# Master_board.net
KiCad netlist of a schematic drawn in EAGLE
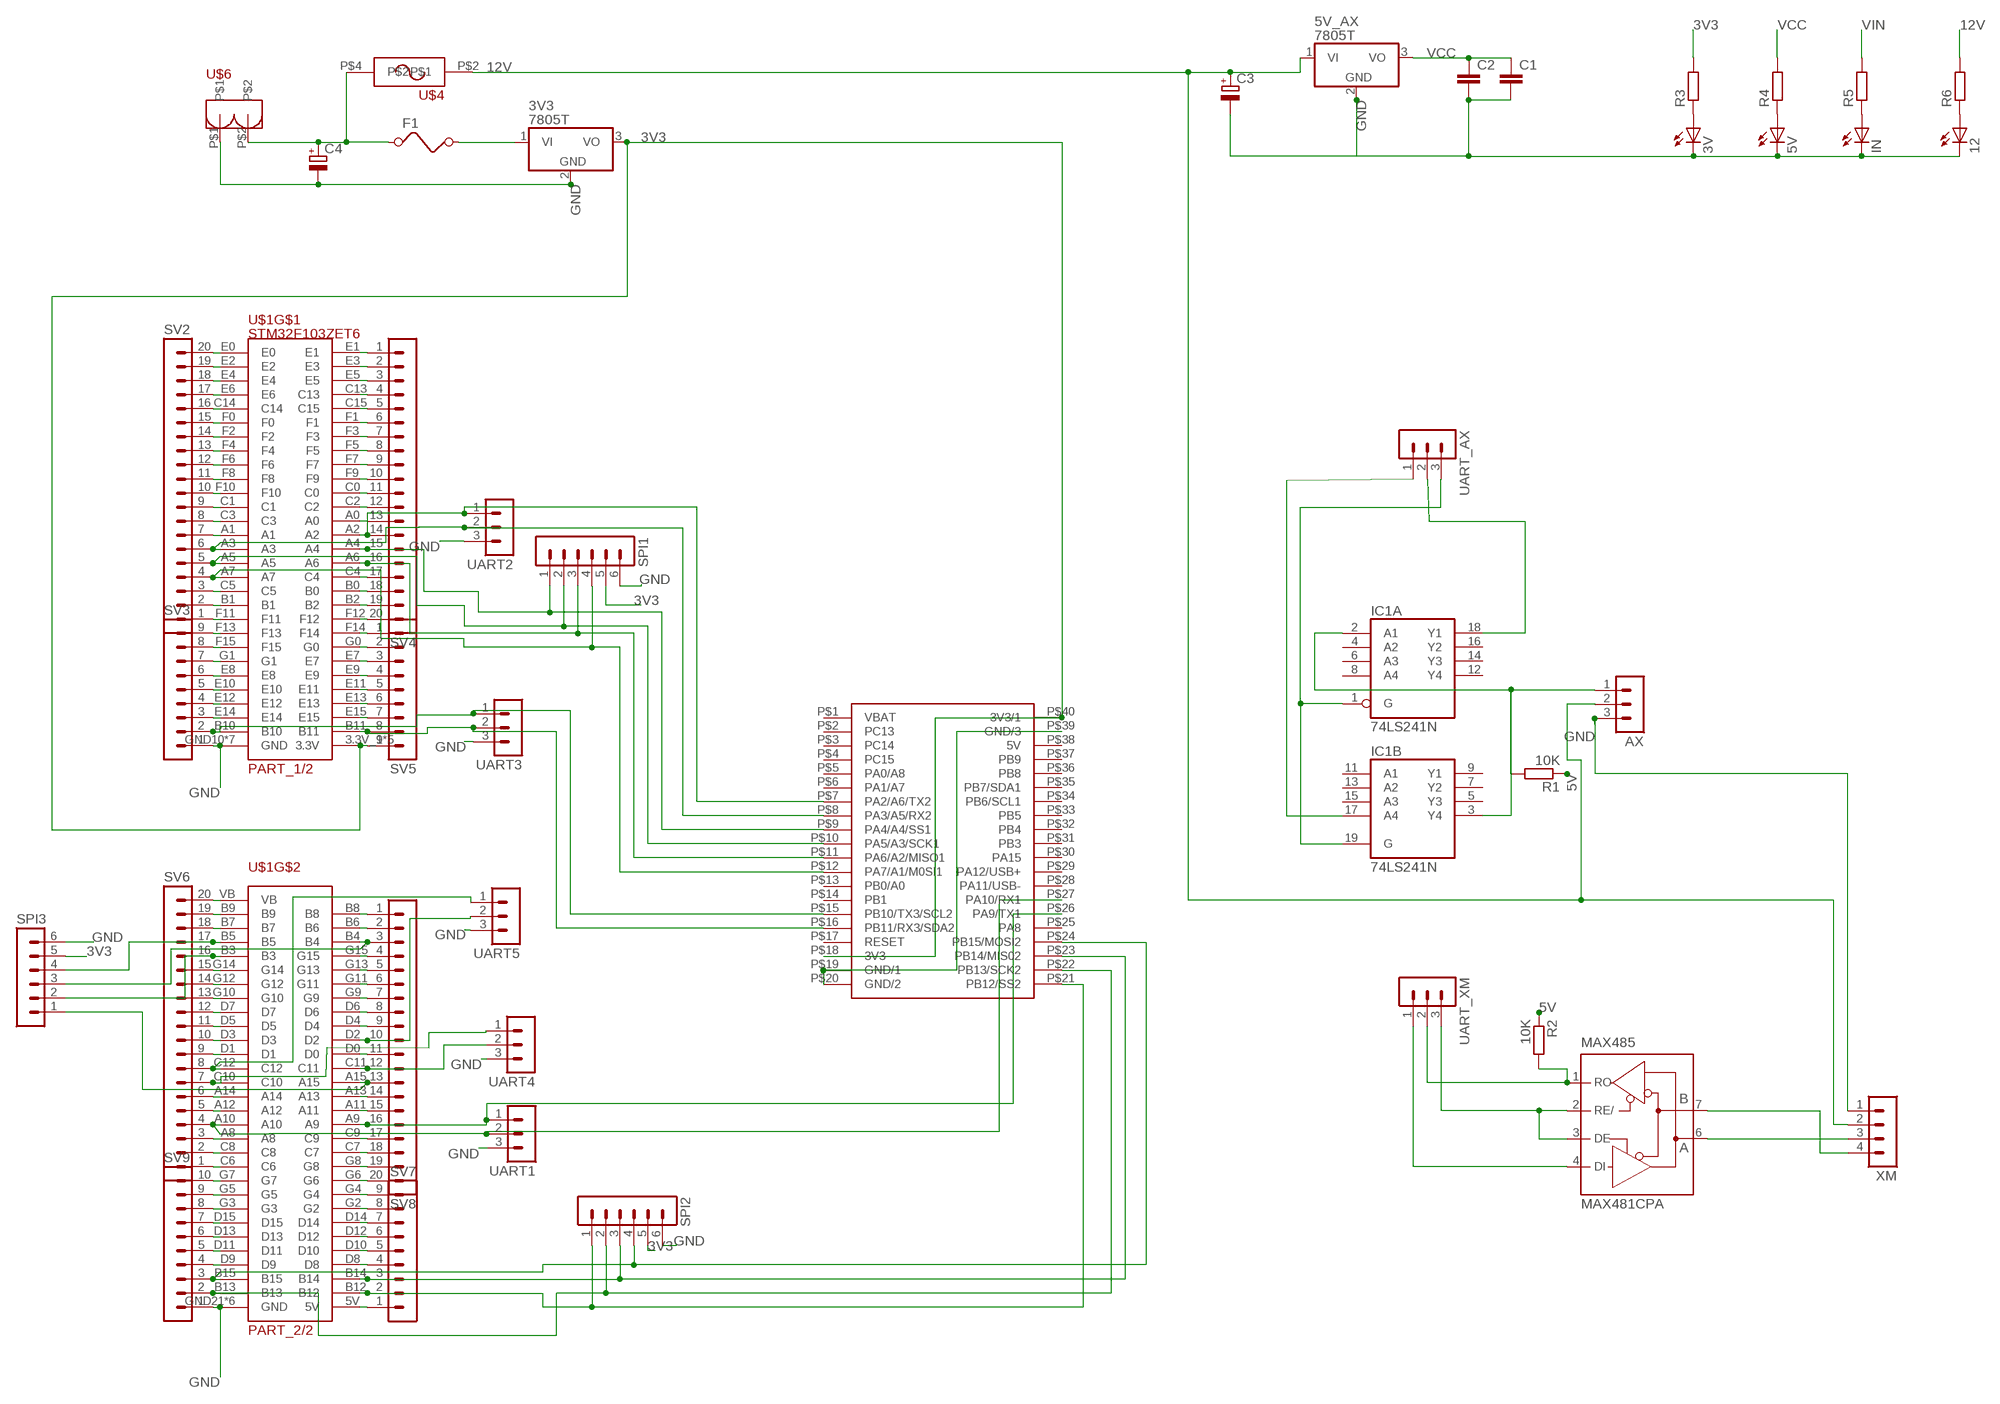
[diagram p0: schematic, sheet 1]

(export (version "E")
  (design (tool "Eeschema 10.0.6"))
  (components
    (comp (ref "3V")
      (value "LED_ELD260")
      (footprint "eagle-import:LED_LD260")
      (libsource (lib "eagle-import") (part "LED_ELD260"))
    )
    (comp (ref "3V3")
      (value "7805T")
      (footprint "eagle-import:TO220H")
      (libsource (lib "eagle-import") (part "78T05"))
    )
    (comp (ref "5V")
      (value "LED_ELD260")
      (footprint "eagle-import:LED_LD260")
      (libsource (lib "eagle-import") (part "LED_ELD260"))
    )
    (comp (ref "5V_AX")
      (value "7805T")
      (footprint "eagle-import:TO220H")
      (libsource (lib "eagle-import") (part "78T05"))
    )
    (comp (ref "12")
      (value "LED_ELD260")
      (footprint "eagle-import:LED_LD260")
      (libsource (lib "eagle-import") (part "LED_ELD260"))
    )
    (comp (ref "AX")
      (value "MA03-1")
      (footprint "eagle-import:MA03-1")
      (libsource (lib "eagle-import") (part "MA03-1"))
    )
    (comp (ref "C1")
      (value "C-EU025-024X044")
      (footprint "eagle-import:C025-024X044")
      (libsource (lib "eagle-import") (part "C-EU025-024X044"))
    )
    (comp (ref "C2")
      (value "C-EU025-024X044")
      (footprint "eagle-import:C025-024X044")
      (libsource (lib "eagle-import") (part "C-EU025-024X044"))
    )
    (comp (ref "C3")
      (value "CPOL-EUE5-10.5")
      (footprint "eagle-import:E5-10,5")
      (libsource (lib "eagle-import") (part "CPOL-EUE5-10.5"))
    )
    (comp (ref "C4")
      (value "CPOL-EUE5-10.5")
      (footprint "eagle-import:E5-10,5")
      (libsource (lib "eagle-import") (part "CPOL-EUE5-10.5"))
    )
    (comp (ref "F1")
      (value "FUSE")
      (footprint "eagle-import:FUSE")
      (libsource (lib "eagle-import") (part "FUSE"))
    )
    (comp (ref "IC1")
      (value "74LS241N")
      (footprint "eagle-import:DIL20")
      (libsource (lib "eagle-import") (part "74241NLS"))
    )
    (comp (ref "IN")
      (value "LED_ELD260")
      (footprint "eagle-import:LED_LD260")
      (libsource (lib "eagle-import") (part "LED_ELD260"))
    )
    (comp (ref "MAX485")
      (value "MAX481CPA")
      (footprint "eagle-import:DIL08")
      (fields (field (name "MPN") "MAX481CPA+"))
      (libsource (lib "eagle-import") (part "MAX481CPA"))
    )
    (comp (ref "R1")
      (value "10K")
      (footprint "eagle-import:0309_12")
      (libsource (lib "eagle-import") (part "R-EU_0309/12"))
    )
    (comp (ref "R2")
      (value "10K")
      (footprint "eagle-import:0309_12")
      (libsource (lib "eagle-import") (part "R-EU_0309/12"))
    )
    (comp (ref "R3")
      (value "R-EU_0204/5")
      (footprint "eagle-import:0204_5")
      (libsource (lib "eagle-import") (part "resistor_348_R-EU_0204/5"))
    )
    (comp (ref "R4")
      (value "R-EU_0204/5")
      (footprint "eagle-import:0204_5")
      (libsource (lib "eagle-import") (part "resistor_348_R-EU_0204/5"))
    )
    (comp (ref "R5")
      (value "R-EU_0204/5")
      (footprint "eagle-import:0204_5")
      (libsource (lib "eagle-import") (part "resistor_348_R-EU_0204/5"))
    )
    (comp (ref "R6")
      (value "R-EU_0204/5")
      (footprint "eagle-import:0204_5")
      (libsource (lib "eagle-import") (part "resistor_348_R-EU_0204/5"))
    )
    (comp (ref "SPI1")
      (value "MA06-1")
      (footprint "eagle-import:MA06-1")
      (libsource (lib "eagle-import") (part "MA06-1"))
    )
    (comp (ref "SPI2")
      (value "MA06-1")
      (footprint "eagle-import:MA06-1")
      (libsource (lib "eagle-import") (part "MA06-1"))
    )
    (comp (ref "SPI3")
      (value "MA06-1")
      (footprint "eagle-import:MA06-1")
      (libsource (lib "eagle-import") (part "MA06-1"))
    )
    (comp (ref "SV2")
      (value "MA20-1L")
      (footprint "eagle-import:MA20-1L")
      (libsource (lib "eagle-import") (part "MA20-1L"))
    )
    (comp (ref "SV3")
      (value "MA09-1")
      (footprint "eagle-import:MA09-1")
      (libsource (lib "eagle-import") (part "MA09-1"))
    )
    (comp (ref "SV4")
      (value "MA20-1L")
      (footprint "eagle-import:MA20-1L")
      (libsource (lib "eagle-import") (part "MA20-1L"))
    )
    (comp (ref "SV5")
      (value "MA09-1")
      (footprint "eagle-import:MA09-1")
      (libsource (lib "eagle-import") (part "MA09-1"))
    )
    (comp (ref "SV6")
      (value "MA20-1L")
      (footprint "eagle-import:MA20-1L")
      (libsource (lib "eagle-import") (part "MA20-1L"))
    )
    (comp (ref "SV7")
      (value "MA09-1")
      (footprint "eagle-import:MA09-1")
      (libsource (lib "eagle-import") (part "MA09-1"))
    )
    (comp (ref "SV8")
      (value "MA20-1L")
      (footprint "eagle-import:MA20-1L")
      (libsource (lib "eagle-import") (part "MA20-1L"))
    )
    (comp (ref "SV9")
      (value "MA10-1")
      (footprint "eagle-import:MA10-1")
      (libsource (lib "eagle-import") (part "MA10-1"))
    )
    (comp (ref "U$1")
      (value "M32F103ZET6_DEV_BOARD")
      (footprint "eagle-import:STM32F103ZET6_DEV_BOARD")
      (libsource (lib "eagle-import") (part "M32F103ZET6_DEV_BOARD"))
    )
    (comp (ref "U$2")
      (value "BLUEPILL")
      (footprint "eagle-import:BLUEPILL")
      (libsource (lib "eagle-import") (part "BLUEPILL"))
    )
    (comp (ref "U$4")
      (value "AUTO_FUSE")
      (footprint "eagle-import:AUTO_FUSE")
      (libsource (lib "eagle-import") (part "AUTO_FUSE"))
    )
    (comp (ref "U$6")
      (value "GREEN_HEADER")
      (footprint "eagle-import:GREEN_HEADER")
      (libsource (lib "eagle-import") (part "GREEN_HEADER"))
    )
    (comp (ref "UART1")
      (value "MA03-1")
      (footprint "eagle-import:MA03-1")
      (libsource (lib "eagle-import") (part "MA03-1"))
    )
    (comp (ref "UART2")
      (value "MA03-1")
      (footprint "eagle-import:MA03-1")
      (libsource (lib "eagle-import") (part "MA03-1"))
    )
    (comp (ref "UART3")
      (value "MA03-1")
      (footprint "eagle-import:MA03-1")
      (libsource (lib "eagle-import") (part "MA03-1"))
    )
    (comp (ref "UART4")
      (value "MA03-1")
      (footprint "eagle-import:MA03-1")
      (libsource (lib "eagle-import") (part "MA03-1"))
    )
    (comp (ref "UART5")
      (value "MA03-1")
      (footprint "eagle-import:MA03-1")
      (libsource (lib "eagle-import") (part "MA03-1"))
    )
    (comp (ref "UART_AX")
      (value "MA03-1")
      (footprint "eagle-import:MA03-1")
      (libsource (lib "eagle-import") (part "MA03-1"))
    )
    (comp (ref "UART_XM")
      (value "MA03-1")
      (footprint "eagle-import:MA03-1")
      (libsource (lib "eagle-import") (part "MA03-1"))
    )
    (comp (ref "XM")
      (value "MA04-1")
      (footprint "eagle-import:MA04-1")
      (libsource (lib "eagle-import") (part "MA04-1"))
    )
  )
  (nets
    (net (code "1") (name "/3V3") (class "Default")
      (node (ref "3V3") (pin "3") (pinfunction "VO_3") (pintype "passive"))
      (node (ref "R3") (pin "2") (pinfunction "2_2") (pintype "passive"))
      (node (ref "SPI1") (pin "5") (pinfunction "5_5") (pintype "passive"))
      (node (ref "SPI2") (pin "5") (pinfunction "5_5") (pintype "passive"))
      (node (ref "SPI3") (pin "5") (pinfunction "5_5") (pintype "passive"))
      (node (ref "SV5") (pin "9") (pinfunction "9_9") (pintype "passive"))
      (node (ref "U$1") (pin "3.3V_1") (pinfunction "3.3V_3.3V_1") (pintype "bidirectional"))
      (node (ref "U$1") (pin "3.3V_2") (pinfunction "3.3V_3.3V_2") (pintype "bidirectional"))
      (node (ref "U$1") (pin "3.3V_3") (pinfunction "3.3V_3.3V_3") (pintype "bidirectional"))
      (node (ref "U$1") (pin "3.3V_4") (pinfunction "3.3V_3.3V_4") (pintype "bidirectional"))
      (node (ref "U$1") (pin "3.3V_5") (pinfunction "3.3V_3.3V_5") (pintype "bidirectional"))
      (node (ref "U$2") (pin "P$18") (pinfunction "3V3_P$18") (pintype "bidirectional"))
      (node (ref "U$2") (pin "P$40") (pinfunction "3V3/1_P$40") (pintype "bidirectional"))
    )
    (net (code "2") (name "/5V") (class "Default")
      (node (ref "R1") (pin "1") (pinfunction "1_1") (pintype "passive"))
      (node (ref "R2") (pin "1") (pinfunction "1_1") (pintype "passive"))
    )
    (net (code "3") (name "/12V") (class "Default")
      (node (ref "5V_AX") (pin "1") (pinfunction "VI_1") (pintype "input"))
      (node (ref "AX") (pin "2") (pinfunction "2_2") (pintype "passive"))
      (node (ref "C3") (pin "+") (pinfunction "+_+") (pintype "passive"))
      (node (ref "R6") (pin "2") (pinfunction "2_2") (pintype "passive"))
      (node (ref "U$4") (pin "P$2") (pinfunction "P$1_P$2") (pintype "bidirectional"))
      (node (ref "XM") (pin "2") (pinfunction "2_2") (pintype "passive"))
    )
    (net (code "4") (name "/GND") (class "Default")
      (node (ref "12") (pin "K") (pinfunction "C_K") (pintype "passive"))
      (node (ref "3V") (pin "K") (pinfunction "C_K") (pintype "passive"))
      (node (ref "3V3") (pin "2") (pinfunction "GND_2") (pintype "passive"))
      (node (ref "5V") (pin "K") (pinfunction "C_K") (pintype "passive"))
      (node (ref "5V_AX") (pin "2") (pinfunction "GND_2") (pintype "passive"))
      (node (ref "AX") (pin "3") (pinfunction "3_3") (pintype "passive"))
      (node (ref "C1") (pin "2") (pinfunction "2_2") (pintype "passive"))
      (node (ref "C2") (pin "2") (pinfunction "2_2") (pintype "passive"))
      (node (ref "C3") (pin "-") (pinfunction "-_-") (pintype "passive"))
      (node (ref "C4") (pin "-") (pinfunction "-_-") (pintype "passive"))
      (node (ref "IN") (pin "K") (pinfunction "C_K") (pintype "passive"))
      (node (ref "SPI1") (pin "6") (pinfunction "6_6") (pintype "passive"))
      (node (ref "SPI2") (pin "6") (pinfunction "6_6") (pintype "passive"))
      (node (ref "SPI3") (pin "6") (pinfunction "6_6") (pintype "passive"))
      (node (ref "SV3") (pin "1") (pinfunction "1_1") (pintype "passive"))
      (node (ref "SV9") (pin "1") (pinfunction "1_1") (pintype "passive"))
      (node (ref "U$1") (pin "GND10") (pinfunction "GND_GND10") (pintype "bidirectional"))
      (node (ref "U$1") (pin "GND11") (pinfunction "GND_GND11") (pintype "bidirectional"))
      (node (ref "U$1") (pin "GND12") (pinfunction "GND_GND12") (pintype "bidirectional"))
      (node (ref "U$1") (pin "GND13") (pinfunction "GND_GND13") (pintype "bidirectional"))
      (node (ref "U$1") (pin "GND14") (pinfunction "GND_GND14") (pintype "bidirectional"))
      (node (ref "U$1") (pin "GND15") (pinfunction "GND_GND15") (pintype "bidirectional"))
      (node (ref "U$1") (pin "GND16") (pinfunction "GND_GND16") (pintype "bidirectional"))
      (node (ref "U$1") (pin "GND21") (pinfunction "GND_GND21") (pintype "bidirectional"))
      (node (ref "U$1") (pin "GND22") (pinfunction "GND_GND22") (pintype "bidirectional"))
      (node (ref "U$1") (pin "GND24") (pinfunction "GND_GND24") (pintype "bidirectional"))
      (node (ref "U$1") (pin "GND25") (pinfunction "GND_GND25") (pintype "bidirectional"))
      (node (ref "U$1") (pin "GND26") (pinfunction "GND_GND26") (pintype "bidirectional"))
      (node (ref "U$1") (pin "GND_20") (pinfunction "GND_GND_20") (pintype "bidirectional"))
      (node (ref "U$2") (pin "P$19") (pinfunction "GND/1_P$19") (pintype "bidirectional"))
      (node (ref "U$2") (pin "P$20") (pinfunction "GND/2_P$20") (pintype "bidirectional"))
      (node (ref "U$2") (pin "P$39") (pinfunction "GND/3_P$39") (pintype "bidirectional"))
      (node (ref "U$6") (pin "P$1") (pinfunction "P$1_P$1") (pintype "bidirectional"))
      (node (ref "UART1") (pin "3") (pinfunction "3_3") (pintype "passive"))
      (node (ref "UART2") (pin "3") (pinfunction "3_3") (pintype "passive"))
      (node (ref "UART3") (pin "3") (pinfunction "3_3") (pintype "passive"))
      (node (ref "UART4") (pin "3") (pinfunction "3_3") (pintype "passive"))
      (node (ref "UART5") (pin "3") (pinfunction "3_3") (pintype "passive"))
      (node (ref "XM") (pin "1") (pinfunction "1_1") (pintype "passive"))
    )
    (net (code "5") (name "/VCC") (class "Default")
      (node (ref "5V_AX") (pin "3") (pinfunction "VO_3") (pintype "passive"))
      (node (ref "C1") (pin "1") (pinfunction "1_1") (pintype "passive"))
      (node (ref "C2") (pin "1") (pinfunction "1_1") (pintype "passive"))
      (node (ref "R4") (pin "2") (pinfunction "2_2") (pintype "passive"))
    )
    (net (code "6") (name "/VIN") (class "Default")
      (node (ref "C4") (pin "+") (pinfunction "+_+") (pintype "passive"))
      (node (ref "F1") (pin "1") (pinfunction "1_1") (pintype "passive"))
      (node (ref "R5") (pin "2") (pinfunction "2_2") (pintype "passive"))
      (node (ref "U$4") (pin "P$4") (pinfunction "P$2_P$4") (pintype "bidirectional"))
      (node (ref "U$6") (pin "P$2") (pinfunction "P$2_P$2") (pintype "bidirectional"))
    )
    (net (code "7") (name "Net-(3V-PadA)") (class "Default")
      (node (ref "3V") (pin "A") (pinfunction "A_A") (pintype "passive"))
      (node (ref "R3") (pin "1") (pinfunction "1_1") (pintype "passive"))
    )
    (net (code "8") (name "Net-(3V3-VI)") (class "Default")
      (node (ref "3V3") (pin "1") (pinfunction "VI_1") (pintype "input"))
      (node (ref "F1") (pin "2") (pinfunction "2_2") (pintype "passive"))
    )
    (net (code "9") (name "Net-(5V-PadA)") (class "Default")
      (node (ref "5V") (pin "A") (pinfunction "A_A") (pintype "passive"))
      (node (ref "R4") (pin "1") (pinfunction "1_1") (pintype "passive"))
    )
    (net (code "10") (name "Net-(12-PadA)") (class "Default")
      (node (ref "12") (pin "A") (pinfunction "A_A") (pintype "passive"))
      (node (ref "R6") (pin "1") (pinfunction "1_1") (pintype "passive"))
    )
    (net (code "11") (name "Net-(IC1A-A1)") (class "Default")
      (node (ref "AX") (pin "1") (pinfunction "1_1") (pintype "passive"))
      (node (ref "IC1") (pin "2") (pinfunction "A1_2") (pintype "input"))
      (node (ref "IC1") (pin "3") (pinfunction "Y4_3") (pintype "tri_state"))
      (node (ref "R1") (pin "2") (pinfunction "2_2") (pintype "passive"))
    )
    (net (code "12") (name "Net-(IC1A-G)") (class "Default")
      (node (ref "IC1") (pin "1") (pinfunction "G_1") (pintype "input"))
      (node (ref "IC1") (pin "19") (pinfunction "G_19") (pintype "input"))
      (node (ref "UART_AX") (pin "3") (pinfunction "3_3") (pintype "passive"))
    )
    (net (code "13") (name "Net-(IC1A-Y1)") (class "Default")
      (node (ref "IC1") (pin "18") (pinfunction "Y1_18") (pintype "tri_state"))
      (node (ref "UART_AX") (pin "2") (pinfunction "2_2") (pintype "passive"))
    )
    (net (code "14") (name "Net-(IC1B-A4)") (class "Default")
      (node (ref "IC1") (pin "17") (pinfunction "A4_17") (pintype "input"))
      (node (ref "UART_AX") (pin "1") (pinfunction "1_1") (pintype "passive"))
    )
    (net (code "15") (name "Net-(IN-PadA)") (class "Default")
      (node (ref "IN") (pin "A") (pinfunction "A_A") (pintype "passive"))
      (node (ref "R5") (pin "1") (pinfunction "1_1") (pintype "passive"))
    )
    (net (code "16") (name "Net-(MAX485A-A)") (class "Default")
      (node (ref "MAX485") (pin "6") (pinfunction "A_6") (pintype "passive"))
      (node (ref "XM") (pin "3") (pinfunction "3_3") (pintype "passive"))
    )
    (net (code "17") (name "Net-(MAX485A-B)") (class "Default")
      (node (ref "MAX485") (pin "7") (pinfunction "B_7") (pintype "passive"))
      (node (ref "XM") (pin "4") (pinfunction "4_4") (pintype "passive"))
    )
    (net (code "18") (name "Net-(MAX485A-DE)") (class "Default")
      (node (ref "MAX485") (pin "2") (pinfunction "RE/_2") (pintype "input"))
      (node (ref "MAX485") (pin "3") (pinfunction "DE_3") (pintype "input"))
      (node (ref "UART_XM") (pin "3") (pinfunction "3_3") (pintype "passive"))
    )
    (net (code "19") (name "Net-(MAX485A-DI)") (class "Default")
      (node (ref "MAX485") (pin "4") (pinfunction "DI_4") (pintype "input"))
      (node (ref "UART_XM") (pin "1") (pinfunction "1_1") (pintype "passive"))
    )
    (net (code "20") (name "Net-(MAX485A-RO)") (class "Default")
      (node (ref "MAX485") (pin "1") (pinfunction "RO_1") (pintype "output"))
      (node (ref "R2") (pin "2") (pinfunction "2_2") (pintype "passive"))
      (node (ref "UART_XM") (pin "2") (pinfunction "2_2") (pintype "passive"))
    )
    (net (code "21") (name "Net-(SPI3-Pad1)") (class "Default")
      (node (ref "SPI3") (pin "1") (pinfunction "1_1") (pintype "passive"))
      (node (ref "SV8") (pin "13") (pinfunction "13_13") (pintype "passive"))
      (node (ref "U$1") (pin "A15") (pinfunction "A15_A15") (pintype "bidirectional"))
    )
    (net (code "22") (name "Net-(SPI3-Pad2)") (class "Default")
      (node (ref "SPI3") (pin "2") (pinfunction "2_2") (pintype "passive"))
      (node (ref "SV6") (pin "16") (pinfunction "16_16") (pintype "passive"))
      (node (ref "U$1") (pin "B3") (pinfunction "B3_B3") (pintype "bidirectional"))
    )
    (net (code "23") (name "Net-(SPI3-Pad3)") (class "Default")
      (node (ref "SPI3") (pin "3") (pinfunction "3_3") (pintype "passive"))
      (node (ref "SV8") (pin "3") (pinfunction "3_3") (pintype "passive"))
      (node (ref "U$1") (pin "B4") (pinfunction "B4_B4") (pintype "bidirectional"))
    )
    (net (code "24") (name "Net-(SPI3-Pad4)") (class "Default")
      (node (ref "SPI3") (pin "4") (pinfunction "4_4") (pintype "passive"))
      (node (ref "SV6") (pin "17") (pinfunction "17_17") (pintype "passive"))
      (node (ref "U$1") (pin "B5") (pinfunction "B5_B5") (pintype "bidirectional"))
    )
    (net (code "25") (name "Net-(SV2-Pad1)") (class "Default")
      (node (ref "SV2") (pin "1") (pinfunction "1_1") (pintype "passive"))
      (node (ref "U$1") (pin "F11") (pinfunction "F11_F11") (pintype "bidirectional"))
    )
    (net (code "26") (name "Net-(SV2-Pad2)") (class "Default")
      (node (ref "SV2") (pin "2") (pinfunction "2_2") (pintype "passive"))
      (node (ref "U$1") (pin "B1") (pinfunction "B1_B1") (pintype "bidirectional"))
    )
    (net (code "27") (name "Net-(SV2-Pad3)") (class "Default")
      (node (ref "SV2") (pin "3") (pinfunction "3_3") (pintype "passive"))
      (node (ref "U$1") (pin "C5") (pinfunction "C5_C5") (pintype "bidirectional"))
    )
    (net (code "28") (name "Net-(SV2-Pad7)") (class "Default")
      (node (ref "SV2") (pin "7") (pinfunction "7_7") (pintype "passive"))
      (node (ref "U$1") (pin "A1") (pinfunction "A1_A1") (pintype "bidirectional"))
    )
    (net (code "29") (name "Net-(SV2-Pad8)") (class "Default")
      (node (ref "SV2") (pin "8") (pinfunction "8_8") (pintype "passive"))
      (node (ref "U$1") (pin "C3") (pinfunction "C3_C3") (pintype "bidirectional"))
    )
    (net (code "30") (name "Net-(SV2-Pad9)") (class "Default")
      (node (ref "SV2") (pin "9") (pinfunction "9_9") (pintype "passive"))
      (node (ref "U$1") (pin "C1") (pinfunction "C1_C1") (pintype "bidirectional"))
    )
    (net (code "31") (name "Net-(SV2-Pad10)") (class "Default")
      (node (ref "SV2") (pin "10") (pinfunction "10_10") (pintype "passive"))
      (node (ref "U$1") (pin "F10") (pinfunction "F10_F10") (pintype "bidirectional"))
    )
    (net (code "32") (name "Net-(SV2-Pad11)") (class "Default")
      (node (ref "SV2") (pin "11") (pinfunction "11_11") (pintype "passive"))
      (node (ref "U$1") (pin "F8") (pinfunction "F8_F8") (pintype "bidirectional"))
    )
    (net (code "33") (name "Net-(SV2-Pad12)") (class "Default")
      (node (ref "SV2") (pin "12") (pinfunction "12_12") (pintype "passive"))
      (node (ref "U$1") (pin "F6") (pinfunction "F6_F6") (pintype "bidirectional"))
    )
    (net (code "34") (name "Net-(SV2-Pad13)") (class "Default")
      (node (ref "SV2") (pin "13") (pinfunction "13_13") (pintype "passive"))
      (node (ref "U$1") (pin "F4") (pinfunction "F4_F4") (pintype "bidirectional"))
    )
    (net (code "35") (name "Net-(SV2-Pad14)") (class "Default")
      (node (ref "SV2") (pin "14") (pinfunction "14_14") (pintype "passive"))
      (node (ref "U$1") (pin "F2") (pinfunction "F2_F2") (pintype "bidirectional"))
    )
    (net (code "36") (name "Net-(SV2-Pad15)") (class "Default")
      (node (ref "SV2") (pin "15") (pinfunction "15_15") (pintype "passive"))
      (node (ref "U$1") (pin "F0") (pinfunction "F0_F0") (pintype "bidirectional"))
    )
    (net (code "37") (name "Net-(SV2-Pad16)") (class "Default")
      (node (ref "SV2") (pin "16") (pinfunction "16_16") (pintype "passive"))
      (node (ref "U$1") (pin "C14") (pinfunction "C14_C14") (pintype "bidirectional"))
    )
    (net (code "38") (name "Net-(SV2-Pad17)") (class "Default")
      (node (ref "SV2") (pin "17") (pinfunction "17_17") (pintype "passive"))
      (node (ref "U$1") (pin "E6") (pinfunction "E6_E6") (pintype "bidirectional"))
    )
    (net (code "39") (name "Net-(SV2-Pad18)") (class "Default")
      (node (ref "SV2") (pin "18") (pinfunction "18_18") (pintype "passive"))
      (node (ref "U$1") (pin "E4") (pinfunction "E4_E4") (pintype "bidirectional"))
    )
    (net (code "40") (name "Net-(SV2-Pad19)") (class "Default")
      (node (ref "SV2") (pin "19") (pinfunction "19_19") (pintype "passive"))
      (node (ref "U$1") (pin "E2") (pinfunction "E2_E2") (pintype "bidirectional"))
    )
    (net (code "41") (name "Net-(SV2-Pad20)") (class "Default")
      (node (ref "SV2") (pin "20") (pinfunction "20_20") (pintype "passive"))
      (node (ref "U$1") (pin "E0") (pinfunction "E0_E0") (pintype "bidirectional"))
    )
    (net (code "42") (name "Net-(SV3-Pad3)") (class "Default")
      (node (ref "SV3") (pin "3") (pinfunction "3_3") (pintype "passive"))
      (node (ref "U$1") (pin "E14") (pinfunction "E14_E14") (pintype "bidirectional"))
    )
    (net (code "43") (name "Net-(SV3-Pad4)") (class "Default")
      (node (ref "SV3") (pin "4") (pinfunction "4_4") (pintype "passive"))
      (node (ref "U$1") (pin "E12") (pinfunction "E12_E12") (pintype "bidirectional"))
    )
    (net (code "44") (name "Net-(SV3-Pad5)") (class "Default")
      (node (ref "SV3") (pin "5") (pinfunction "5_5") (pintype "passive"))
      (node (ref "U$1") (pin "E10") (pinfunction "E10_E10") (pintype "bidirectional"))
    )
    (net (code "45") (name "Net-(SV3-Pad6)") (class "Default")
      (node (ref "SV3") (pin "6") (pinfunction "6_6") (pintype "passive"))
      (node (ref "U$1") (pin "E8") (pinfunction "E8_E8") (pintype "bidirectional"))
    )
    (net (code "46") (name "Net-(SV3-Pad7)") (class "Default")
      (node (ref "SV3") (pin "7") (pinfunction "7_7") (pintype "passive"))
      (node (ref "U$1") (pin "G1") (pinfunction "G1_G1") (pintype "bidirectional"))
    )
    (net (code "47") (name "Net-(SV3-Pad8)") (class "Default")
      (node (ref "SV3") (pin "8") (pinfunction "8_8") (pintype "passive"))
      (node (ref "U$1") (pin "F15") (pinfunction "F15_F15") (pintype "bidirectional"))
    )
    (net (code "48") (name "Net-(SV3-Pad9)") (class "Default")
      (node (ref "SV3") (pin "9") (pinfunction "9_9") (pintype "passive"))
      (node (ref "U$1") (pin "F13") (pinfunction "F13_F13") (pintype "bidirectional"))
    )
    (net (code "49") (name "Net-(SV4-Pad1)") (class "Default")
      (node (ref "SV4") (pin "1") (pinfunction "1_1") (pintype "passive"))
      (node (ref "U$1") (pin "E1") (pinfunction "E1_E1") (pintype "bidirectional"))
    )
    (net (code "50") (name "Net-(SV4-Pad2)") (class "Default")
      (node (ref "SV4") (pin "2") (pinfunction "2_2") (pintype "passive"))
      (node (ref "U$1") (pin "E3") (pinfunction "E3_E3") (pintype "bidirectional"))
    )
    (net (code "51") (name "Net-(SV4-Pad3)") (class "Default")
      (node (ref "SV4") (pin "3") (pinfunction "3_3") (pintype "passive"))
      (node (ref "U$1") (pin "E5") (pinfunction "E5_E5") (pintype "bidirectional"))
    )
    (net (code "52") (name "Net-(SV4-Pad4)") (class "Default")
      (node (ref "SV4") (pin "4") (pinfunction "4_4") (pintype "passive"))
      (node (ref "U$1") (pin "C13") (pinfunction "C13_C13") (pintype "bidirectional"))
    )
    (net (code "53") (name "Net-(SV4-Pad5)") (class "Default")
      (node (ref "SV4") (pin "5") (pinfunction "5_5") (pintype "passive"))
      (node (ref "U$1") (pin "C15") (pinfunction "C15_C15") (pintype "bidirectional"))
    )
    (net (code "54") (name "Net-(SV4-Pad6)") (class "Default")
      (node (ref "SV4") (pin "6") (pinfunction "6_6") (pintype "passive"))
      (node (ref "U$1") (pin "F1") (pinfunction "F1_F1") (pintype "bidirectional"))
    )
    (net (code "55") (name "Net-(SV4-Pad7)") (class "Default")
      (node (ref "SV4") (pin "7") (pinfunction "7_7") (pintype "passive"))
      (node (ref "U$1") (pin "F3") (pinfunction "F3_F3") (pintype "bidirectional"))
    )
    (net (code "56") (name "Net-(SV4-Pad8)") (class "Default")
      (node (ref "SV4") (pin "8") (pinfunction "8_8") (pintype "passive"))
      (node (ref "U$1") (pin "F5") (pinfunction "F5_F5") (pintype "bidirectional"))
    )
    (net (code "57") (name "Net-(SV4-Pad9)") (class "Default")
      (node (ref "SV4") (pin "9") (pinfunction "9_9") (pintype "passive"))
      (node (ref "U$1") (pin "F7") (pinfunction "F7_F7") (pintype "bidirectional"))
    )
    (net (code "58") (name "Net-(SV4-Pad10)") (class "Default")
      (node (ref "SV4") (pin "10") (pinfunction "10_10") (pintype "passive"))
      (node (ref "U$1") (pin "F9") (pinfunction "F9_F9") (pintype "bidirectional"))
    )
    (net (code "59") (name "Net-(SV4-Pad11)") (class "Default")
      (node (ref "SV4") (pin "11") (pinfunction "11_11") (pintype "passive"))
      (node (ref "U$1") (pin "C0") (pinfunction "C0_C0") (pintype "bidirectional"))
    )
    (net (code "60") (name "Net-(SV4-Pad12)") (class "Default")
      (node (ref "SV4") (pin "12") (pinfunction "12_12") (pintype "passive"))
      (node (ref "U$1") (pin "C2") (pinfunction "C2_C2") (pintype "bidirectional"))
    )
    (net (code "61") (name "Net-(SV4-Pad13)") (class "Default")
      (node (ref "SV4") (pin "13") (pinfunction "13_13") (pintype "passive"))
      (node (ref "U$1") (pin "A0") (pinfunction "A0_A0") (pintype "bidirectional"))
    )
    (net (code "62") (name "Net-(SV4-Pad17)") (class "Default")
      (node (ref "SV4") (pin "17") (pinfunction "17_17") (pintype "passive"))
      (node (ref "U$1") (pin "C4") (pinfunction "C4_C4") (pintype "bidirectional"))
    )
    (net (code "63") (name "Net-(SV4-Pad18)") (class "Default")
      (node (ref "SV4") (pin "18") (pinfunction "18_18") (pintype "passive"))
      (node (ref "U$1") (pin "B0") (pinfunction "B0_B0") (pintype "bidirectional"))
    )
    (net (code "64") (name "Net-(SV4-Pad19)") (class "Default")
      (node (ref "SV4") (pin "19") (pinfunction "19_19") (pintype "passive"))
      (node (ref "U$1") (pin "B2") (pinfunction "B2_B2") (pintype "bidirectional"))
    )
    (net (code "65") (name "Net-(SV4-Pad20)") (class "Default")
      (node (ref "SV4") (pin "20") (pinfunction "20_20") (pintype "passive"))
      (node (ref "U$1") (pin "F12") (pinfunction "F12_F12") (pintype "bidirectional"))
    )
    (net (code "66") (name "Net-(SV5-Pad1)") (class "Default")
      (node (ref "SV5") (pin "1") (pinfunction "1_1") (pintype "passive"))
      (node (ref "U$1") (pin "F14") (pinfunction "F14_F14") (pintype "bidirectional"))
    )
    (net (code "67") (name "Net-(SV5-Pad2)") (class "Default")
      (node (ref "SV5") (pin "2") (pinfunction "2_2") (pintype "passive"))
      (node (ref "U$1") (pin "G0") (pinfunction "G0_G0") (pintype "bidirectional"))
    )
    (net (code "68") (name "Net-(SV5-Pad3)") (class "Default")
      (node (ref "SV5") (pin "3") (pinfunction "3_3") (pintype "passive"))
      (node (ref "U$1") (pin "E7") (pinfunction "E7_E7") (pintype "bidirectional"))
    )
    (net (code "69") (name "Net-(SV5-Pad4)") (class "Default")
      (node (ref "SV5") (pin "4") (pinfunction "4_4") (pintype "passive"))
      (node (ref "U$1") (pin "E9") (pinfunction "E9_E9") (pintype "bidirectional"))
    )
    (net (code "70") (name "Net-(SV5-Pad5)") (class "Default")
      (node (ref "SV5") (pin "5") (pinfunction "5_5") (pintype "passive"))
      (node (ref "U$1") (pin "E11") (pinfunction "E11_E11") (pintype "bidirectional"))
    )
    (net (code "71") (name "Net-(SV5-Pad6)") (class "Default")
      (node (ref "SV5") (pin "6") (pinfunction "6_6") (pintype "passive"))
      (node (ref "U$1") (pin "E13") (pinfunction "E13_E13") (pintype "bidirectional"))
    )
    (net (code "72") (name "Net-(SV5-Pad7)") (class "Default")
      (node (ref "SV5") (pin "7") (pinfunction "7_7") (pintype "passive"))
      (node (ref "U$1") (pin "E15") (pinfunction "E15_E15") (pintype "bidirectional"))
    )
    (net (code "73") (name "Net-(SV6-Pad1)") (class "Default")
      (node (ref "SV6") (pin "1") (pinfunction "1_1") (pintype "passive"))
      (node (ref "U$1") (pin "C6") (pinfunction "C6_C6") (pintype "bidirectional"))
    )
    (net (code "74") (name "Net-(SV6-Pad2)") (class "Default")
      (node (ref "SV6") (pin "2") (pinfunction "2_2") (pintype "passive"))
      (node (ref "U$1") (pin "C8") (pinfunction "C8_C8") (pintype "bidirectional"))
    )
    (net (code "75") (name "Net-(SV6-Pad3)") (class "Default")
      (node (ref "SV6") (pin "3") (pinfunction "3_3") (pintype "passive"))
      (node (ref "U$1") (pin "A8") (pinfunction "A8_A8") (pintype "bidirectional"))
    )
    (net (code "76") (name "Net-(SV6-Pad5)") (class "Default")
      (node (ref "SV6") (pin "5") (pinfunction "5_5") (pintype "passive"))
      (node (ref "U$1") (pin "A12") (pinfunction "A12_A12") (pintype "bidirectional"))
    )
    (net (code "77") (name "Net-(SV6-Pad6)") (class "Default")
      (node (ref "SV6") (pin "6") (pinfunction "6_6") (pintype "passive"))
      (node (ref "U$1") (pin "A14") (pinfunction "A14_A14") (pintype "bidirectional"))
    )
    (net (code "78") (name "Net-(SV6-Pad7)") (class "Default")
      (node (ref "SV6") (pin "7") (pinfunction "7_7") (pintype "passive"))
      (node (ref "U$1") (pin "C10") (pinfunction "C10_C10") (pintype "bidirectional"))
      (node (ref "UART4") (pin "1") (pinfunction "1_1") (pintype "passive"))
    )
    (net (code "79") (name "Net-(SV6-Pad8)") (class "Default")
      (node (ref "SV6") (pin "8") (pinfunction "8_8") (pintype "passive"))
      (node (ref "U$1") (pin "C12") (pinfunction "C12_C12") (pintype "bidirectional"))
      (node (ref "UART5") (pin "1") (pinfunction "1_1") (pintype "passive"))
    )
    (net (code "80") (name "Net-(SV6-Pad9)") (class "Default")
      (node (ref "SV6") (pin "9") (pinfunction "9_9") (pintype "passive"))
      (node (ref "U$1") (pin "D1") (pinfunction "D1_D1") (pintype "bidirectional"))
    )
    (net (code "81") (name "Net-(SV6-Pad10)") (class "Default")
      (node (ref "SV6") (pin "10") (pinfunction "10_10") (pintype "passive"))
      (node (ref "U$1") (pin "D3") (pinfunction "D3_D3") (pintype "bidirectional"))
    )
    (net (code "82") (name "Net-(SV6-Pad11)") (class "Default")
      (node (ref "SV6") (pin "11") (pinfunction "11_11") (pintype "passive"))
      (node (ref "U$1") (pin "D5") (pinfunction "D5_D5") (pintype "bidirectional"))
    )
    (net (code "83") (name "Net-(SV6-Pad12)") (class "Default")
      (node (ref "SV6") (pin "12") (pinfunction "12_12") (pintype "passive"))
      (node (ref "U$1") (pin "D7") (pinfunction "D7_D7") (pintype "bidirectional"))
    )
    (net (code "84") (name "Net-(SV6-Pad13)") (class "Default")
      (node (ref "SV6") (pin "13") (pinfunction "13_13") (pintype "passive"))
      (node (ref "U$1") (pin "G10") (pinfunction "G10_G10") (pintype "bidirectional"))
    )
    (net (code "85") (name "Net-(SV6-Pad14)") (class "Default")
      (node (ref "SV6") (pin "14") (pinfunction "14_14") (pintype "passive"))
      (node (ref "U$1") (pin "G12") (pinfunction "G12_G12") (pintype "bidirectional"))
    )
    (net (code "86") (name "Net-(SV6-Pad15)") (class "Default")
      (node (ref "SV6") (pin "15") (pinfunction "15_15") (pintype "passive"))
      (node (ref "U$1") (pin "G14") (pinfunction "G14_G14") (pintype "bidirectional"))
    )
    (net (code "87") (name "Net-(SV6-Pad18)") (class "Default")
      (node (ref "SV6") (pin "18") (pinfunction "18_18") (pintype "passive"))
      (node (ref "U$1") (pin "B7") (pinfunction "B7_B7") (pintype "bidirectional"))
    )
    (net (code "88") (name "Net-(SV6-Pad19)") (class "Default")
      (node (ref "SV6") (pin "19") (pinfunction "19_19") (pintype "passive"))
      (node (ref "U$1") (pin "B9") (pinfunction "B9_B9") (pintype "bidirectional"))
    )
    (net (code "89") (name "Net-(SV6-Pad20)") (class "Default")
      (node (ref "SV6") (pin "20") (pinfunction "20_20") (pintype "passive"))
      (node (ref "U$1") (pin "VB") (pinfunction "VB_VB") (pintype "bidirectional"))
    )
    (net (code "90") (name "Net-(SV7-Pad1)") (class "Default")
      (node (ref "SV7") (pin "1") (pinfunction "1_1") (pintype "passive"))
      (node (ref "U$1") (pin "5V") (pinfunction "5V_5V") (pintype "bidirectional"))
    )
    (net (code "91") (name "Net-(SV7-Pad4)") (class "Default")
      (node (ref "SV7") (pin "4") (pinfunction "4_4") (pintype "passive"))
      (node (ref "U$1") (pin "D8") (pinfunction "D8_D8") (pintype "bidirectional"))
    )
    (net (code "92") (name "Net-(SV7-Pad5)") (class "Default")
      (node (ref "SV7") (pin "5") (pinfunction "5_5") (pintype "passive"))
      (node (ref "U$1") (pin "D10") (pinfunction "D10_D10") (pintype "bidirectional"))
    )
    (net (code "93") (name "Net-(SV7-Pad6)") (class "Default")
      (node (ref "SV7") (pin "6") (pinfunction "6_6") (pintype "passive"))
      (node (ref "U$1") (pin "D12") (pinfunction "D12_D12") (pintype "bidirectional"))
    )
    (net (code "94") (name "Net-(SV7-Pad7)") (class "Default")
      (node (ref "SV7") (pin "7") (pinfunction "7_7") (pintype "passive"))
      (node (ref "U$1") (pin "D14") (pinfunction "D14_D14") (pintype "bidirectional"))
    )
    (net (code "95") (name "Net-(SV7-Pad8)") (class "Default")
      (node (ref "SV7") (pin "8") (pinfunction "8_8") (pintype "passive"))
      (node (ref "U$1") (pin "G2") (pinfunction "G2_G2") (pintype "bidirectional"))
    )
    (net (code "96") (name "Net-(SV7-Pad9)") (class "Default")
      (node (ref "SV7") (pin "9") (pinfunction "9_9") (pintype "passive"))
      (node (ref "U$1") (pin "G4") (pinfunction "G4_G4") (pintype "bidirectional"))
    )
    (net (code "97") (name "Net-(SV8-Pad1)") (class "Default")
      (node (ref "SV8") (pin "1") (pinfunction "1_1") (pintype "passive"))
      (node (ref "U$1") (pin "B8") (pinfunction "B8_B8") (pintype "bidirectional"))
    )
    (net (code "98") (name "Net-(SV8-Pad2)") (class "Default")
      (node (ref "SV8") (pin "2") (pinfunction "2_2") (pintype "passive"))
      (node (ref "U$1") (pin "B6") (pinfunction "B6_B6") (pintype "bidirectional"))
    )
    (net (code "99") (name "Net-(SV8-Pad4)") (class "Default")
      (node (ref "SV8") (pin "4") (pinfunction "4_4") (pintype "passive"))
      (node (ref "U$1") (pin "G15") (pinfunction "G15_G15") (pintype "bidirectional"))
    )
    (net (code "100") (name "Net-(SV8-Pad5)") (class "Default")
      (node (ref "SV8") (pin "5") (pinfunction "5_5") (pintype "passive"))
      (node (ref "U$1") (pin "G13") (pinfunction "G13_G13") (pintype "bidirectional"))
    )
    (net (code "101") (name "Net-(SV8-Pad6)") (class "Default")
      (node (ref "SV8") (pin "6") (pinfunction "6_6") (pintype "passive"))
      (node (ref "U$1") (pin "G11") (pinfunction "G11_G11") (pintype "bidirectional"))
    )
    (net (code "102") (name "Net-(SV8-Pad7)") (class "Default")
      (node (ref "SV8") (pin "7") (pinfunction "7_7") (pintype "passive"))
      (node (ref "U$1") (pin "G9") (pinfunction "G9_G9") (pintype "bidirectional"))
    )
    (net (code "103") (name "Net-(SV8-Pad8)") (class "Default")
      (node (ref "SV8") (pin "8") (pinfunction "8_8") (pintype "passive"))
      (node (ref "U$1") (pin "D6") (pinfunction "D6_D6") (pintype "bidirectional"))
    )
    (net (code "104") (name "Net-(SV8-Pad9)") (class "Default")
      (node (ref "SV8") (pin "9") (pinfunction "9_9") (pintype "passive"))
      (node (ref "U$1") (pin "D4") (pinfunction "D4_D4") (pintype "bidirectional"))
    )
    (net (code "105") (name "Net-(SV8-Pad10)") (class "Default")
      (node (ref "SV8") (pin "10") (pinfunction "10_10") (pintype "passive"))
      (node (ref "U$1") (pin "D2") (pinfunction "D2_D2") (pintype "bidirectional"))
      (node (ref "UART5") (pin "2") (pinfunction "2_2") (pintype "passive"))
    )
    (net (code "106") (name "Net-(SV8-Pad11)") (class "Default")
      (node (ref "SV8") (pin "11") (pinfunction "11_11") (pintype "passive"))
      (node (ref "U$1") (pin "D0") (pinfunction "D0_D0") (pintype "bidirectional"))
    )
    (net (code "107") (name "Net-(SV8-Pad12)") (class "Default")
      (node (ref "SV8") (pin "12") (pinfunction "12_12") (pintype "passive"))
      (node (ref "U$1") (pin "C11") (pinfunction "C11_C11") (pintype "bidirectional"))
      (node (ref "UART4") (pin "2") (pinfunction "2_2") (pintype "passive"))
    )
    (net (code "108") (name "Net-(SV8-Pad14)") (class "Default")
      (node (ref "SV8") (pin "14") (pinfunction "14_14") (pintype "passive"))
      (node (ref "U$1") (pin "A13") (pinfunction "A13_A13") (pintype "bidirectional"))
    )
    (net (code "109") (name "Net-(SV8-Pad15)") (class "Default")
      (node (ref "SV8") (pin "15") (pinfunction "15_15") (pintype "passive"))
      (node (ref "U$1") (pin "A11") (pinfunction "A11_A11") (pintype "bidirectional"))
    )
    (net (code "110") (name "Net-(SV8-Pad17)") (class "Default")
      (node (ref "SV8") (pin "17") (pinfunction "17_17") (pintype "passive"))
      (node (ref "U$1") (pin "C9") (pinfunction "C9_C9") (pintype "bidirectional"))
    )
    (net (code "111") (name "Net-(SV8-Pad18)") (class "Default")
      (node (ref "SV8") (pin "18") (pinfunction "18_18") (pintype "passive"))
      (node (ref "U$1") (pin "C7") (pinfunction "C7_C7") (pintype "bidirectional"))
    )
    (net (code "112") (name "Net-(SV8-Pad19)") (class "Default")
      (node (ref "SV8") (pin "19") (pinfunction "19_19") (pintype "passive"))
      (node (ref "U$1") (pin "G8") (pinfunction "G8_G8") (pintype "bidirectional"))
    )
    (net (code "113") (name "Net-(SV8-Pad20)") (class "Default")
      (node (ref "SV8") (pin "20") (pinfunction "20_20") (pintype "passive"))
      (node (ref "U$1") (pin "G6") (pinfunction "G6_G6") (pintype "bidirectional"))
    )
    (net (code "114") (name "Net-(SV9-Pad4)") (class "Default")
      (node (ref "SV9") (pin "4") (pinfunction "4_4") (pintype "passive"))
      (node (ref "U$1") (pin "D9") (pinfunction "D9_D9") (pintype "bidirectional"))
    )
    (net (code "115") (name "Net-(SV9-Pad5)") (class "Default")
      (node (ref "SV9") (pin "5") (pinfunction "5_5") (pintype "passive"))
      (node (ref "U$1") (pin "D11") (pinfunction "D11_D11") (pintype "bidirectional"))
    )
    (net (code "116") (name "Net-(SV9-Pad6)") (class "Default")
      (node (ref "SV9") (pin "6") (pinfunction "6_6") (pintype "passive"))
      (node (ref "U$1") (pin "D13") (pinfunction "D13_D13") (pintype "bidirectional"))
    )
    (net (code "117") (name "Net-(SV9-Pad7)") (class "Default")
      (node (ref "SV9") (pin "7") (pinfunction "7_7") (pintype "passive"))
      (node (ref "U$1") (pin "D15") (pinfunction "D15_D15") (pintype "bidirectional"))
    )
    (net (code "118") (name "Net-(SV9-Pad8)") (class "Default")
      (node (ref "SV9") (pin "8") (pinfunction "8_8") (pintype "passive"))
      (node (ref "U$1") (pin "G3") (pinfunction "G3_G3") (pintype "bidirectional"))
    )
    (net (code "119") (name "Net-(SV9-Pad9)") (class "Default")
      (node (ref "SV9") (pin "9") (pinfunction "9_9") (pintype "passive"))
      (node (ref "U$1") (pin "G5") (pinfunction "G5_G5") (pintype "bidirectional"))
    )
    (net (code "120") (name "Net-(SV9-Pad10)") (class "Default")
      (node (ref "SV9") (pin "10") (pinfunction "10_10") (pintype "passive"))
      (node (ref "U$1") (pin "G7") (pinfunction "G7_G7") (pintype "bidirectional"))
    )
    (net (code "121") (name "Net-(U$2-PA2{slash}A6{slash}TX2)") (class "Default")
      (node (ref "SV4") (pin "14") (pinfunction "14_14") (pintype "passive"))
      (node (ref "U$1") (pin "A2") (pinfunction "A2_A2") (pintype "bidirectional"))
      (node (ref "U$2") (pin "P$7") (pinfunction "PA2/A6/TX2_P$7") (pintype "bidirectional"))
      (node (ref "UART2") (pin "1") (pinfunction "1_1") (pintype "passive"))
    )
    (net (code "122") (name "Net-(U$2-PA3{slash}A5{slash}RX2)") (class "Default")
      (node (ref "SV2") (pin "6") (pinfunction "6_6") (pintype "passive"))
      (node (ref "U$1") (pin "A3") (pinfunction "A3_A3") (pintype "bidirectional"))
      (node (ref "U$2") (pin "P$8") (pinfunction "PA3/A5/RX2_P$8") (pintype "bidirectional"))
      (node (ref "UART2") (pin "2") (pinfunction "2_2") (pintype "passive"))
    )
    (net (code "123") (name "Net-(U$2-PA4{slash}A4{slash}SS1)") (class "Default")
      (node (ref "SPI1") (pin "1") (pinfunction "1_1") (pintype "passive"))
      (node (ref "SV4") (pin "15") (pinfunction "15_15") (pintype "passive"))
      (node (ref "U$1") (pin "A4") (pinfunction "A4_A4") (pintype "bidirectional"))
      (node (ref "U$2") (pin "P$9") (pinfunction "PA4/A4/SS1_P$9") (pintype "bidirectional"))
    )
    (net (code "124") (name "Net-(U$2-PA5{slash}A3{slash}SCK1)") (class "Default")
      (node (ref "SPI1") (pin "2") (pinfunction "2_2") (pintype "passive"))
      (node (ref "SV2") (pin "5") (pinfunction "5_5") (pintype "passive"))
      (node (ref "U$1") (pin "A5") (pinfunction "A5_A5") (pintype "bidirectional"))
      (node (ref "U$2") (pin "P$10") (pinfunction "PA5/A3/SCK1_P$10") (pintype "bidirectional"))
    )
    (net (code "125") (name "Net-(U$2-PA6{slash}A2{slash}MISO1)") (class "Default")
      (node (ref "SPI1") (pin "3") (pinfunction "3_3") (pintype "passive"))
      (node (ref "SV4") (pin "16") (pinfunction "16_16") (pintype "passive"))
      (node (ref "U$1") (pin "A6") (pinfunction "A6_A6") (pintype "bidirectional"))
      (node (ref "U$2") (pin "P$11") (pinfunction "PA6/A2/MISO1_P$11") (pintype "bidirectional"))
    )
    (net (code "126") (name "Net-(U$2-PA7{slash}A1{slash}M0SI1)") (class "Default")
      (node (ref "SPI1") (pin "4") (pinfunction "4_4") (pintype "passive"))
      (node (ref "SV2") (pin "4") (pinfunction "4_4") (pintype "passive"))
      (node (ref "U$1") (pin "A7") (pinfunction "A7_A7") (pintype "bidirectional"))
      (node (ref "U$2") (pin "P$12") (pinfunction "PA7/A1/M0SI1_P$12") (pintype "bidirectional"))
    )
    (net (code "127") (name "Net-(U$2-PA9{slash}TX1)") (class "Default")
      (node (ref "SV8") (pin "16") (pinfunction "16_16") (pintype "passive"))
      (node (ref "U$1") (pin "A9") (pinfunction "A9_A9") (pintype "bidirectional"))
      (node (ref "U$2") (pin "P$26") (pinfunction "PA9/TX1_P$26") (pintype "bidirectional"))
      (node (ref "UART1") (pin "1") (pinfunction "1_1") (pintype "passive"))
    )
    (net (code "128") (name "Net-(U$2-PA10{slash}RX1)") (class "Default")
      (node (ref "SV6") (pin "4") (pinfunction "4_4") (pintype "passive"))
      (node (ref "U$1") (pin "A10") (pinfunction "A10_A10") (pintype "bidirectional"))
      (node (ref "U$2") (pin "P$27") (pinfunction "PA10/RX1_P$27") (pintype "bidirectional"))
      (node (ref "UART1") (pin "2") (pinfunction "2_2") (pintype "passive"))
    )
    (net (code "129") (name "Net-(U$2-PB10{slash}TX3{slash}SCL2)") (class "Default")
      (node (ref "SV3") (pin "2") (pinfunction "2_2") (pintype "passive"))
      (node (ref "U$1") (pin "B10") (pinfunction "B10_B10") (pintype "bidirectional"))
      (node (ref "U$2") (pin "P$15") (pinfunction "PB10/TX3/SCL2_P$15") (pintype "bidirectional"))
      (node (ref "UART3") (pin "1") (pinfunction "1_1") (pintype "passive"))
    )
    (net (code "130") (name "Net-(U$2-PB11{slash}RX3{slash}SDA2)") (class "Default")
      (node (ref "SV5") (pin "8") (pinfunction "8_8") (pintype "passive"))
      (node (ref "U$1") (pin "B11") (pinfunction "B11_B11") (pintype "bidirectional"))
      (node (ref "U$2") (pin "P$16") (pinfunction "PB11/RX3/SDA2_P$16") (pintype "bidirectional"))
      (node (ref "UART3") (pin "2") (pinfunction "2_2") (pintype "passive"))
    )
    (net (code "131") (name "Net-(U$2-PB12{slash}SS2)") (class "Default")
      (node (ref "SPI2") (pin "1") (pinfunction "1_1") (pintype "passive"))
      (node (ref "SV7") (pin "2") (pinfunction "2_2") (pintype "passive"))
      (node (ref "U$1") (pin "B12") (pinfunction "B12_B12") (pintype "bidirectional"))
      (node (ref "U$2") (pin "P$21") (pinfunction "PB12/SS2_P$21") (pintype "bidirectional"))
    )
    (net (code "132") (name "Net-(U$2-PB13{slash}SCK2)") (class "Default")
      (node (ref "SPI2") (pin "2") (pinfunction "2_2") (pintype "passive"))
      (node (ref "SV9") (pin "2") (pinfunction "2_2") (pintype "passive"))
      (node (ref "U$1") (pin "B13") (pinfunction "B13_B13") (pintype "bidirectional"))
      (node (ref "U$2") (pin "P$22") (pinfunction "PB13/SCK2_P$22") (pintype "bidirectional"))
    )
    (net (code "133") (name "Net-(U$2-PB14{slash}MIS02)") (class "Default")
      (node (ref "SPI2") (pin "3") (pinfunction "3_3") (pintype "passive"))
      (node (ref "SV7") (pin "3") (pinfunction "3_3") (pintype "passive"))
      (node (ref "U$1") (pin "B14") (pinfunction "B14_B14") (pintype "bidirectional"))
      (node (ref "U$2") (pin "P$23") (pinfunction "PB14/MIS02_P$23") (pintype "bidirectional"))
    )
    (net (code "134") (name "Net-(U$2-PB15{slash}MOSI2)") (class "Default")
      (node (ref "SPI2") (pin "4") (pinfunction "4_4") (pintype "passive"))
      (node (ref "SV9") (pin "3") (pinfunction "3_3") (pintype "passive"))
      (node (ref "U$1") (pin "B15") (pinfunction "B15_B15") (pintype "bidirectional"))
      (node (ref "U$2") (pin "P$24") (pinfunction "PB15/MOSI2_P$24") (pintype "bidirectional"))
    )
    (net (code "135") (name "unconnected-(IC1A-A2-Pad4)") (class "Default")
      (node (ref "IC1") (pin "4") (pinfunction "A2_4") (pintype "input"))
    )
    (net (code "136") (name "unconnected-(IC1A-A3-Pad6)") (class "Default")
      (node (ref "IC1") (pin "6") (pinfunction "A3_6") (pintype "input"))
    )
    (net (code "137") (name "unconnected-(IC1A-A4-Pad8)") (class "Default")
      (node (ref "IC1") (pin "8") (pinfunction "A4_8") (pintype "input"))
    )
    (net (code "138") (name "unconnected-(IC1A-Y2-Pad16)") (class "Default")
      (node (ref "IC1") (pin "16") (pinfunction "Y2_16") (pintype "tri_state"))
    )
    (net (code "139") (name "unconnected-(IC1A-Y3-Pad14)") (class "Default")
      (node (ref "IC1") (pin "14") (pinfunction "Y3_14") (pintype "tri_state"))
    )
    (net (code "140") (name "unconnected-(IC1A-Y4-Pad12)") (class "Default")
      (node (ref "IC1") (pin "12") (pinfunction "Y4_12") (pintype "tri_state"))
    )
    (net (code "141") (name "unconnected-(IC1B-A1-Pad11)") (class "Default")
      (node (ref "IC1") (pin "11") (pinfunction "A1_11") (pintype "input"))
    )
    (net (code "142") (name "unconnected-(IC1B-A2-Pad13)") (class "Default")
      (node (ref "IC1") (pin "13") (pinfunction "A2_13") (pintype "input"))
    )
    (net (code "143") (name "unconnected-(IC1B-A3-Pad15)") (class "Default")
      (node (ref "IC1") (pin "15") (pinfunction "A3_15") (pintype "input"))
    )
    (net (code "144") (name "unconnected-(IC1B-Y1-Pad9)") (class "Default")
      (node (ref "IC1") (pin "9") (pinfunction "Y1_9") (pintype "tri_state"))
    )
    (net (code "145") (name "unconnected-(IC1B-Y2-Pad7)") (class "Default")
      (node (ref "IC1") (pin "7") (pinfunction "Y2_7") (pintype "tri_state"))
    )
    (net (code "146") (name "unconnected-(IC1B-Y3-Pad5)") (class "Default")
      (node (ref "IC1") (pin "5") (pinfunction "Y3_5") (pintype "tri_state"))
    )
    (net (code "147") (name "unconnected-(U$2-5V-PadP$38)") (class "Default")
      (node (ref "U$2") (pin "P$38") (pinfunction "5V_P$38") (pintype "bidirectional"))
    )
    (net (code "148") (name "unconnected-(U$2-PA0{slash}A8-PadP$5)") (class "Default")
      (node (ref "U$2") (pin "P$5") (pinfunction "PA0/A8_P$5") (pintype "bidirectional"))
    )
    (net (code "149") (name "unconnected-(U$2-PA1{slash}A7-PadP$6)") (class "Default")
      (node (ref "U$2") (pin "P$6") (pinfunction "PA1/A7_P$6") (pintype "bidirectional"))
    )
    (net (code "150") (name "unconnected-(U$2-PA8-PadP$25)") (class "Default")
      (node (ref "U$2") (pin "P$25") (pinfunction "PA8_P$25") (pintype "bidirectional"))
    )
    (net (code "151") (name "unconnected-(U$2-PA11{slash}USB--PadP$28)") (class "Default")
      (node (ref "U$2") (pin "P$28") (pinfunction "PA11/USB-_P$28") (pintype "bidirectional"))
    )
    (net (code "152") (name "unconnected-(U$2-PA12{slash}USB+-PadP$29)") (class "Default")
      (node (ref "U$2") (pin "P$29") (pinfunction "PA12/USB+_P$29") (pintype "bidirectional"))
    )
    (net (code "153") (name "unconnected-(U$2-PA15-PadP$30)") (class "Default")
      (node (ref "U$2") (pin "P$30") (pinfunction "PA15_P$30") (pintype "bidirectional"))
    )
    (net (code "154") (name "unconnected-(U$2-PB0{slash}A0-PadP$13)") (class "Default")
      (node (ref "U$2") (pin "P$13") (pinfunction "PB0/A0_P$13") (pintype "bidirectional"))
    )
    (net (code "155") (name "unconnected-(U$2-PB1-PadP$14)") (class "Default")
      (node (ref "U$2") (pin "P$14") (pinfunction "PB1_P$14") (pintype "bidirectional"))
    )
    (net (code "156") (name "unconnected-(U$2-PB3-PadP$31)") (class "Default")
      (node (ref "U$2") (pin "P$31") (pinfunction "PB3_P$31") (pintype "bidirectional"))
    )
    (net (code "157") (name "unconnected-(U$2-PB4-PadP$32)") (class "Default")
      (node (ref "U$2") (pin "P$32") (pinfunction "PB4_P$32") (pintype "bidirectional"))
    )
    (net (code "158") (name "unconnected-(U$2-PB5-PadP$33)") (class "Default")
      (node (ref "U$2") (pin "P$33") (pinfunction "PB5_P$33") (pintype "bidirectional"))
    )
    (net (code "159") (name "unconnected-(U$2-PB6{slash}SCL1-PadP$34)") (class "Default")
      (node (ref "U$2") (pin "P$34") (pinfunction "PB6/SCL1_P$34") (pintype "bidirectional"))
    )
    (net (code "160") (name "unconnected-(U$2-PB7{slash}SDA1-PadP$35)") (class "Default")
      (node (ref "U$2") (pin "P$35") (pinfunction "PB7/SDA1_P$35") (pintype "bidirectional"))
    )
    (net (code "161") (name "unconnected-(U$2-PB8-PadP$36)") (class "Default")
      (node (ref "U$2") (pin "P$36") (pinfunction "PB8_P$36") (pintype "bidirectional"))
    )
    (net (code "162") (name "unconnected-(U$2-PB9-PadP$37)") (class "Default")
      (node (ref "U$2") (pin "P$37") (pinfunction "PB9_P$37") (pintype "bidirectional"))
    )
    (net (code "163") (name "unconnected-(U$2-PC13-PadP$2)") (class "Default")
      (node (ref "U$2") (pin "P$2") (pinfunction "PC13_P$2") (pintype "bidirectional"))
    )
    (net (code "164") (name "unconnected-(U$2-PC14-PadP$3)") (class "Default")
      (node (ref "U$2") (pin "P$3") (pinfunction "PC14_P$3") (pintype "bidirectional"))
    )
    (net (code "165") (name "unconnected-(U$2-PC15-PadP$4)") (class "Default")
      (node (ref "U$2") (pin "P$4") (pinfunction "PC15_P$4") (pintype "bidirectional"))
    )
    (net (code "166") (name "unconnected-(U$2-RESET-PadP$17)") (class "Default")
      (node (ref "U$2") (pin "P$17") (pinfunction "RESET_P$17") (pintype "bidirectional"))
    )
    (net (code "167") (name "unconnected-(U$2-VBAT-PadP$1)") (class "Default")
      (node (ref "U$2") (pin "P$1") (pinfunction "VBAT_P$1") (pintype "bidirectional"))
    )
  )
)
